# ECMeter-M0.net
KiCad netlist of a schematic drawn in EAGLE
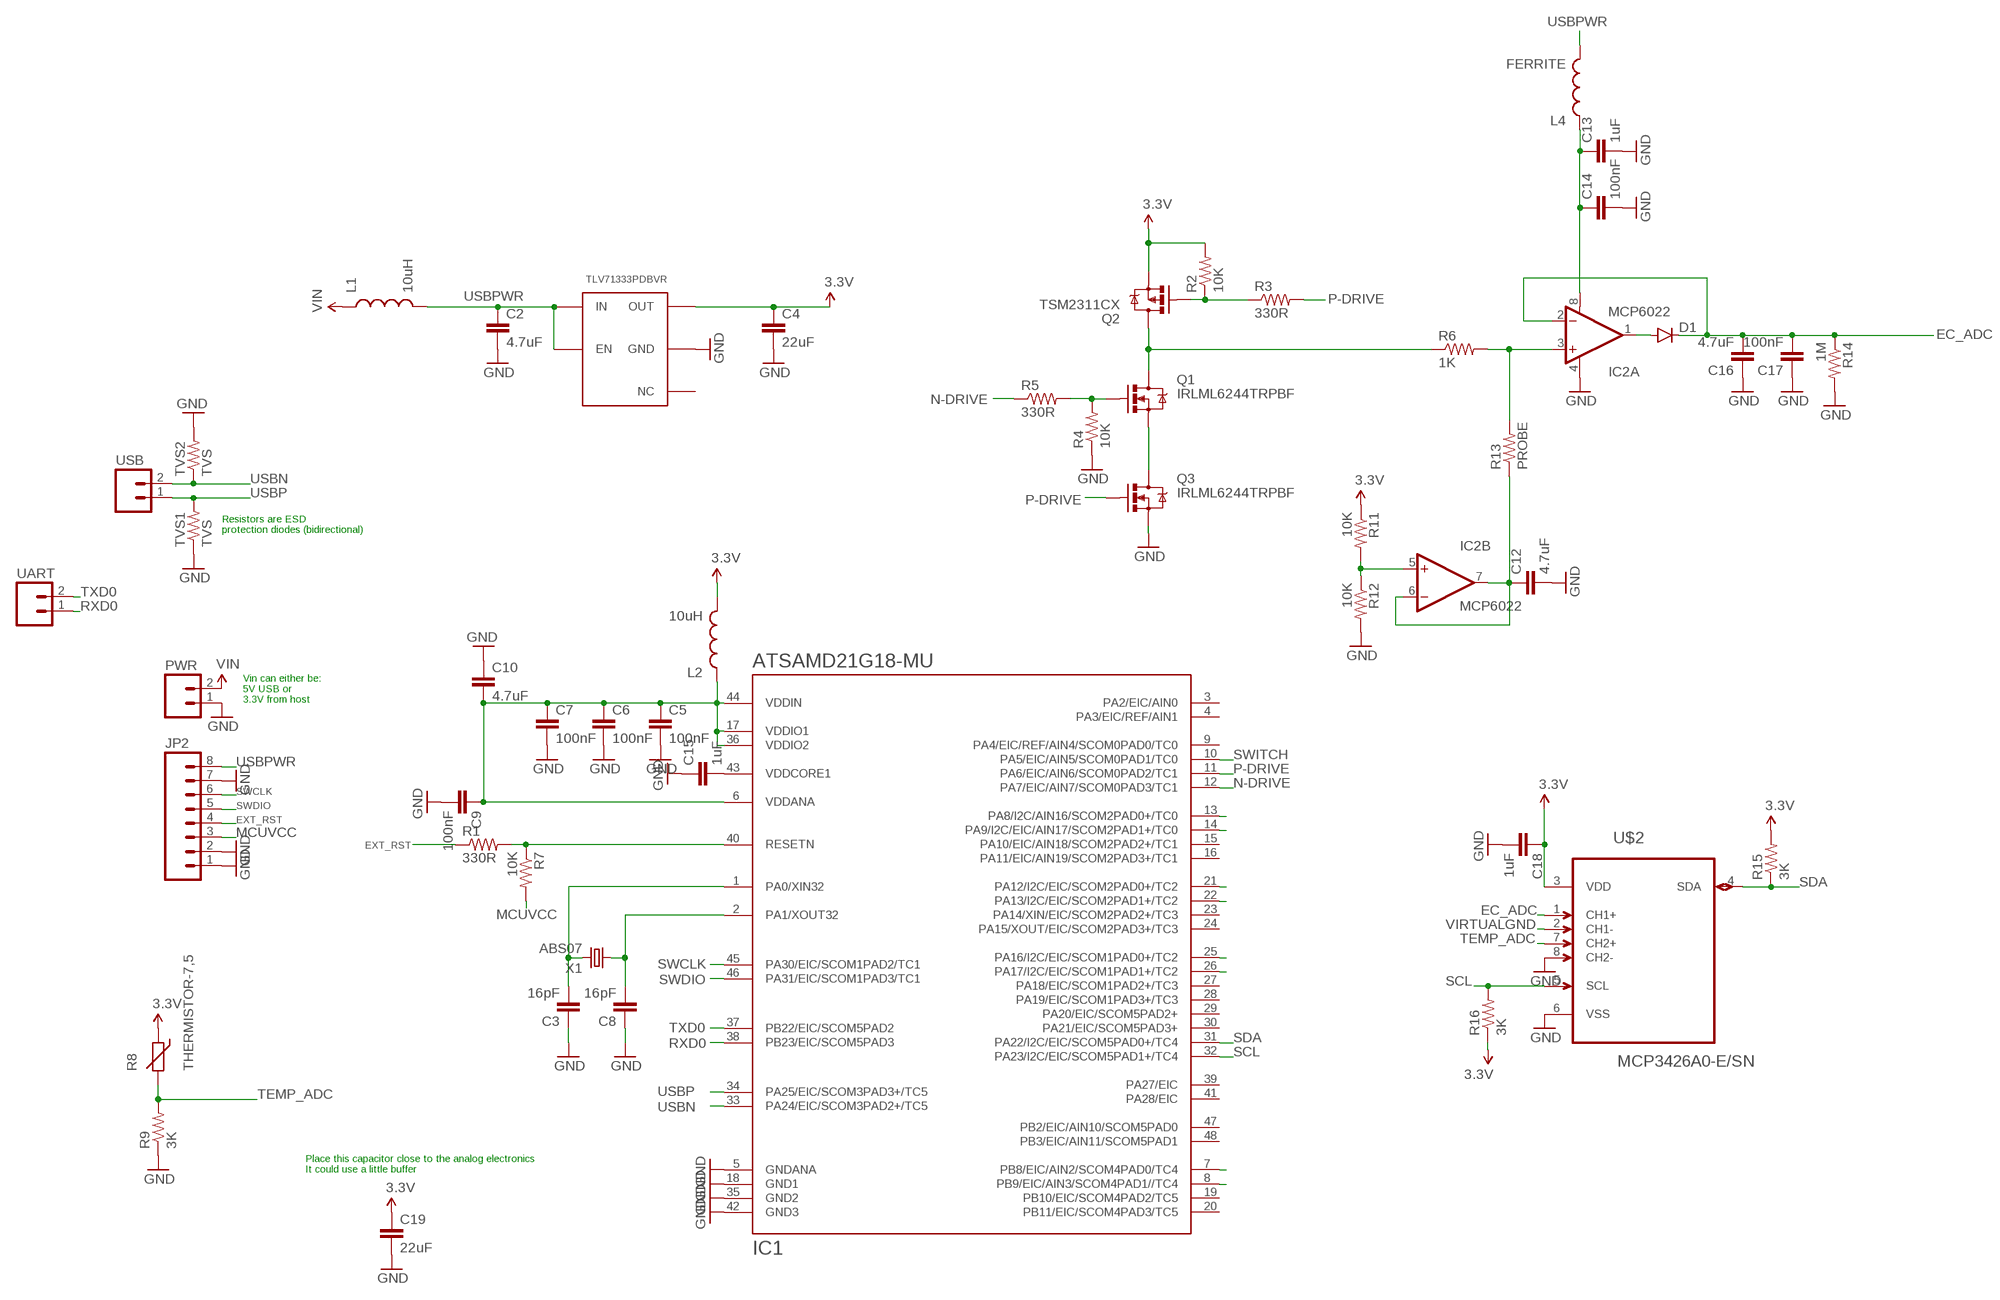
[diagram p0: schematic, sheet 1]

(export (version "E")
  (design (tool "Eeschema 10.0.6"))
  (components
    (comp (ref "C2")
      (value "4.7uF")
      (footprint "eagle-import:0805")
      (libsource (lib "eagle-import") (part "SparkFun-Passives_CAP0805"))
    )
    (comp (ref "C3")
      (value "16pF")
      (footprint "eagle-import:0402-CAP")
      (libsource (lib "eagle-import") (part "CAP0402-CAP"))
    )
    (comp (ref "C4")
      (value "22uF")
      (footprint "eagle-import:0805")
      (libsource (lib "eagle-import") (part "CAP0805"))
    )
    (comp (ref "C5")
      (value "100nF")
      (footprint "eagle-import:0603-CAP")
      (libsource (lib "eagle-import") (part "SparkFun-Passives_CAP0603-CAP"))
    )
    (comp (ref "C6")
      (value "100nF")
      (footprint "eagle-import:0603-CAP")
      (libsource (lib "eagle-import") (part "SparkFun-Passives_CAP0603-CAP"))
    )
    (comp (ref "C7")
      (value "100nF")
      (footprint "eagle-import:0603-CAP")
      (libsource (lib "eagle-import") (part "SparkFun-Passives_CAP0603-CAP"))
    )
    (comp (ref "C8")
      (value "16pF")
      (footprint "eagle-import:0402-CAP")
      (libsource (lib "eagle-import") (part "CAP0402-CAP"))
    )
    (comp (ref "C9")
      (value "100nF")
      (footprint "eagle-import:0603-CAP")
      (libsource (lib "eagle-import") (part "SparkFun-Passives_CAP0603-CAP"))
    )
    (comp (ref "C10")
      (value "4.7uF")
      (footprint "eagle-import:0805")
      (libsource (lib "eagle-import") (part "CAP0805"))
    )
    (comp (ref "C12")
      (value "4.7uF")
      (footprint "eagle-import:0805")
      (libsource (lib "eagle-import") (part "CAP0805"))
    )
    (comp (ref "C13")
      (value "1uF")
      (footprint "eagle-import:0603-CAP")
      (libsource (lib "eagle-import") (part "SparkFun-Passives_CAP0603-CAP"))
    )
    (comp (ref "C14")
      (value "100nF")
      (footprint "eagle-import:0603-CAP")
      (libsource (lib "eagle-import") (part "SparkFun-Passives_CAP0603-CAP"))
    )
    (comp (ref "C15")
      (value "1uF")
      (footprint "eagle-import:0603-CAP")
      (libsource (lib "eagle-import") (part "SparkFun-Passives_CAP0603-CAP"))
    )
    (comp (ref "C16")
      (value "4.7uF")
      (footprint "eagle-import:0805")
      (libsource (lib "eagle-import") (part "SparkFun-Passives_CAP0805"))
    )
    (comp (ref "C17")
      (value "100nF")
      (footprint "eagle-import:0603-CAP")
      (libsource (lib "eagle-import") (part "SparkFun-Passives_CAP0603-CAP"))
    )
    (comp (ref "C18")
      (value "1uF")
      (footprint "eagle-import:0603-CAP")
      (libsource (lib "eagle-import") (part "SparkFun-Passives_CAP0603-CAP"))
    )
    (comp (ref "C19")
      (value "22uF")
      (footprint "eagle-import:0805")
      (libsource (lib "eagle-import") (part "CAP0805"))
    )
    (comp (ref "D1")
      (value "DIODESOD123")
      (footprint "eagle-import:SOD-123")
      (libsource (lib "eagle-import") (part "DIODESOD123"))
    )
    (comp (ref "IC1")
      (value "ATSAMD21G18-MU")
      (footprint "eagle-import:QFN48")
      (libsource (lib "eagle-import") (part "ATSAMD21G18-MU"))
    )
    (comp (ref "IC2")
      (value "MCP6022")
      (footprint "eagle-import:SO08")
      (libsource (lib "eagle-import") (part "OPAMP-DUALU"))
    )
    (comp (ref "JP2")
      (value "M08NO_SILK_FEMALE_PTH")
      (footprint "eagle-import:1X08_NO_SILK")
      (libsource (lib "eagle-import") (part "M08NO_SILK_FEMALE_PTH"))
    )
    (comp (ref "L1")
      (value "10uH")
      (footprint "eagle-import:0805")
      (libsource (lib "eagle-import") (part "INDUCTOR0805"))
    )
    (comp (ref "L2")
      (value "10uH")
      (footprint "eagle-import:0805")
      (libsource (lib "eagle-import") (part "INDUCTOR0805"))
    )
    (comp (ref "L4")
      (value "FERRITE")
      (footprint "eagle-import:0603")
      (libsource (lib "eagle-import") (part "INDUCTOR0603"))
    )
    (comp (ref "PWR")
      (value "M02LOCK_LONGPADS")
      (footprint "eagle-import:1X02_LOCK_LONGPADS")
      (libsource (lib "eagle-import") (part "M02LOCK_LONGPADS"))
    )
    (comp (ref "Q1")
      (value "IRLML6244TRPBF")
      (footprint "eagle-import:SOT23-3")
      (libsource (lib "eagle-import") (part "MOSFET-NCHANNELAO3404A"))
    )
    (comp (ref "Q2")
      (value "TSM2311CX")
      (footprint "eagle-import:SOT23-3")
      (libsource (lib "eagle-import") (part "MOSFET-PCHANNEL"))
    )
    (comp (ref "Q3")
      (value "IRLML6244TRPBF")
      (footprint "eagle-import:SOT23-3")
      (libsource (lib "eagle-import") (part "MOSFET-NCHANNELAO3404A"))
    )
    (comp (ref "R1")
      (value "330R")
      (footprint "eagle-import:0603-RES")
      (libsource (lib "eagle-import") (part "SparkFun-Resistors_RESISTOR0603-RES"))
    )
    (comp (ref "R2")
      (value "10K")
      (footprint "eagle-import:0603-RES")
      (libsource (lib "eagle-import") (part "SparkFun-Resistors_RESISTOR0603-RES"))
    )
    (comp (ref "R3")
      (value "330R")
      (footprint "eagle-import:0603-RES")
      (libsource (lib "eagle-import") (part "SparkFun-Resistors_RESISTOR0603-RES"))
    )
    (comp (ref "R4")
      (value "10K")
      (footprint "eagle-import:0603-RES")
      (libsource (lib "eagle-import") (part "SparkFun-Resistors_RESISTOR0603-RES"))
    )
    (comp (ref "R5")
      (value "330R")
      (footprint "eagle-import:0603-RES")
      (libsource (lib "eagle-import") (part "SparkFun-Resistors_RESISTOR0603-RES"))
    )
    (comp (ref "R6")
      (value "1K")
      (footprint "eagle-import:1206")
      (libsource (lib "eagle-import") (part "SparkFun-Resistors_RESISTOR1206"))
    )
    (comp (ref "R7")
      (value "10K")
      (footprint "eagle-import:0603-RES")
      (libsource (lib "eagle-import") (part "SparkFun-Resistors_RESISTOR0603-RES"))
    )
    (comp (ref "R8")
      (value "THERMISTOR-7,5")
      (footprint "eagle-import:R-7,5")
      (libsource (lib "eagle-import") (part "THERMISTOR-7,5"))
    )
    (comp (ref "R9")
      (value "3K")
      (footprint "eagle-import:0603-RES")
      (libsource (lib "eagle-import") (part "SparkFun-Resistors_RESISTOR0603-RES"))
    )
    (comp (ref "R11")
      (value "10K")
      (footprint "eagle-import:0603-RES")
      (libsource (lib "eagle-import") (part "SparkFun-Resistors_RESISTOR0603-RES"))
    )
    (comp (ref "R12")
      (value "10K")
      (footprint "eagle-import:0603-RES")
      (libsource (lib "eagle-import") (part "SparkFun-Resistors_RESISTOR0603-RES"))
    )
    (comp (ref "R13")
      (value "PROBE")
      (footprint "eagle-import:AXIAL-0.6")
      (libsource (lib "eagle-import") (part "RESISTORPTH-1W"))
    )
    (comp (ref "R14")
      (value "1M")
      (footprint "eagle-import:0603-RES")
      (libsource (lib "eagle-import") (part "SparkFun-Resistors_RESISTOR0603-RES"))
    )
    (comp (ref "R15")
      (value "3K")
      (footprint "eagle-import:0603-RES")
      (libsource (lib "eagle-import") (part "SparkFun-Resistors_RESISTOR0603-RES"))
    )
    (comp (ref "R16")
      (value "3K")
      (footprint "eagle-import:0603-RES")
      (libsource (lib "eagle-import") (part "SparkFun-Resistors_RESISTOR0603-RES"))
    )
    (comp (ref "TVS1")
      (value "TVS")
      (footprint "eagle-import:0603-RES")
      (libsource (lib "eagle-import") (part "RESISTOR0603-RES"))
    )
    (comp (ref "TVS2")
      (value "TVS")
      (footprint "eagle-import:0603-RES")
      (libsource (lib "eagle-import") (part "RESISTOR0603-RES"))
    )
    (comp (ref "U$1")
      (value "TLV71333PDBVR")
      (footprint "eagle-import:TLV71333PDBVR")
      (libsource (lib "eagle-import") (part "TLV71333PDBVR"))
    )
    (comp (ref "U$2")
      (value "MCP3426A0-E/SN")
      (footprint "eagle-import:SOIC127P600X175-8N")
      (libsource (lib "eagle-import") (part "MCP3426A0-E/SN"))
    )
    (comp (ref "UART")
      (value "M02LOCK_LONGPADS")
      (footprint "eagle-import:1X02_LOCK_LONGPADS")
      (libsource (lib "eagle-import") (part "M02LOCK_LONGPADS"))
    )
    (comp (ref "USB")
      (value "M02LOCK_LONGPADS")
      (footprint "eagle-import:1X02_LOCK_LONGPADS")
      (libsource (lib "eagle-import") (part "M02LOCK_LONGPADS"))
    )
    (comp (ref "X1")
      (value "ABS07")
      (footprint "eagle-import:ABS07")
      (libsource (lib "eagle-import") (part "ABS07"))
    )
  )
  (nets
    (net (code "1") (name "/EC_ADC") (class "Default")
      (node (ref "C16") (pin "2") (pinfunction "2_2") (pintype "passive"))
      (node (ref "C17") (pin "2") (pinfunction "2_2") (pintype "passive"))
      (node (ref "D1") (pin "C") (pinfunction "C_C") (pintype "passive"))
      (node (ref "IC2") (pin "2") (pinfunction "-IN_2") (pintype "input"))
      (node (ref "R14") (pin "1") (pinfunction "1_1") (pintype "passive"))
      (node (ref "U$2") (pin "1") (pinfunction "CH1+_1") (pintype "input"))
    )
    (net (code "2") (name "/EXT_RST") (class "Default")
      (node (ref "JP2") (pin "4") (pinfunction "4_4") (pintype "passive"))
      (node (ref "R1") (pin "1") (pinfunction "1_1") (pintype "passive"))
    )
    (net (code "3") (name "/MCUVCC") (class "Default")
      (node (ref "C10") (pin "2") (pinfunction "2_2") (pintype "passive"))
      (node (ref "C5") (pin "1") (pinfunction "1_1") (pintype "passive"))
      (node (ref "C6") (pin "1") (pinfunction "1_1") (pintype "passive"))
      (node (ref "C7") (pin "1") (pinfunction "1_1") (pintype "passive"))
      (node (ref "C9") (pin "1") (pinfunction "1_1") (pintype "passive"))
      (node (ref "IC1") (pin "17") (pinfunction "VDDIO1_17") (pintype "power_in"))
      (node (ref "IC1") (pin "36") (pinfunction "VDDIO2_36") (pintype "power_in"))
      (node (ref "IC1") (pin "44") (pinfunction "VDDIN_44") (pintype "power_in"))
      (node (ref "IC1") (pin "6") (pinfunction "VDDANA_6") (pintype "power_in"))
      (node (ref "JP2") (pin "3") (pinfunction "3_3") (pintype "passive"))
      (node (ref "L2") (pin "1") (pinfunction "1_1") (pintype "passive"))
      (node (ref "R7") (pin "2") (pinfunction "2_2") (pintype "passive"))
    )
    (net (code "4") (name "/N-DRIVE") (class "Default")
      (node (ref "IC1") (pin "12") (pinfunction "PA7/EIC/AIN7/SCOM0PAD3/TC1_12") (pintype "bidirectional"))
      (node (ref "R5") (pin "1") (pinfunction "1_1") (pintype "passive"))
    )
    (net (code "5") (name "/P-DRIVE") (class "Default")
      (node (ref "IC1") (pin "11") (pinfunction "PA6/EIC/AIN6/SCOM0PAD2/TC1_11") (pintype "bidirectional"))
      (node (ref "Q3") (pin "1") (pinfunction "G_1") (pintype "passive"))
      (node (ref "R3") (pin "2") (pinfunction "2_2") (pintype "passive"))
    )
    (net (code "6") (name "/RXD0") (class "Default")
      (node (ref "IC1") (pin "38") (pinfunction "PB23/EIC/SCOM5PAD3_38") (pintype "bidirectional"))
      (node (ref "UART") (pin "1") (pinfunction "1_1") (pintype "passive"))
    )
    (net (code "7") (name "/SCL") (class "Default")
      (node (ref "IC1") (pin "32") (pinfunction "PA23/I2C/EIC/SCOM5PAD1+/TC4_32") (pintype "bidirectional"))
      (node (ref "R16") (pin "2") (pinfunction "2_2") (pintype "passive"))
      (node (ref "U$2") (pin "5") (pinfunction "SCL_5") (pintype "input"))
    )
    (net (code "8") (name "/SDA") (class "Default")
      (node (ref "IC1") (pin "31") (pinfunction "PA22/I2C/EIC/SCOM5PAD0+/TC4_31") (pintype "bidirectional"))
      (node (ref "R15") (pin "1") (pinfunction "1_1") (pintype "passive"))
      (node (ref "U$2") (pin "4") (pinfunction "SDA_4") (pintype "bidirectional"))
    )
    (net (code "9") (name "/SWCLK") (class "Default")
      (node (ref "IC1") (pin "45") (pinfunction "PA30/EIC/SCOM1PAD2/TC1_45") (pintype "bidirectional"))
      (node (ref "JP2") (pin "6") (pinfunction "6_6") (pintype "passive"))
    )
    (net (code "10") (name "/SWDIO") (class "Default")
      (node (ref "IC1") (pin "46") (pinfunction "PA31/EIC/SCOM1PAD3/TC1_46") (pintype "bidirectional"))
      (node (ref "JP2") (pin "5") (pinfunction "5_5") (pintype "passive"))
    )
    (net (code "11") (name "/SWITCH") (class "Default")
      (node (ref "IC1") (pin "10") (pinfunction "PA5/EIC/AIN5/SCOM0PAD1/TC0_10") (pintype "bidirectional"))
    )
    (net (code "12") (name "/TEMP_ADC") (class "Default")
      (node (ref "R8") (pin "2") (pinfunction "2_2") (pintype "passive"))
      (node (ref "R9") (pin "2") (pinfunction "2_2") (pintype "passive"))
      (node (ref "U$2") (pin "7") (pinfunction "CH2+_7") (pintype "input"))
    )
    (net (code "13") (name "/TXD0") (class "Default")
      (node (ref "IC1") (pin "37") (pinfunction "PB22/EIC/SCOM5PAD2_37") (pintype "bidirectional"))
      (node (ref "UART") (pin "2") (pinfunction "2_2") (pintype "passive"))
    )
    (net (code "14") (name "/USBN") (class "Default")
      (node (ref "IC1") (pin "33") (pinfunction "PA24/EIC/SCOM3PAD2+/TC5_33") (pintype "bidirectional"))
      (node (ref "TVS2") (pin "1") (pinfunction "1_1") (pintype "passive"))
      (node (ref "USB") (pin "2") (pinfunction "2_2") (pintype "passive"))
    )
    (net (code "15") (name "/USBP") (class "Default")
      (node (ref "IC1") (pin "34") (pinfunction "PA25/EIC/SCOM3PAD3+/TC5_34") (pintype "bidirectional"))
      (node (ref "TVS1") (pin "2") (pinfunction "2_2") (pintype "passive"))
      (node (ref "USB") (pin "1") (pinfunction "1_1") (pintype "passive"))
    )
    (net (code "16") (name "/USBPWR") (class "Default")
      (node (ref "C2") (pin "1") (pinfunction "1_1") (pintype "passive"))
      (node (ref "JP2") (pin "8") (pinfunction "8_8") (pintype "passive"))
      (node (ref "L1") (pin "2") (pinfunction "2_2") (pintype "passive"))
      (node (ref "L4") (pin "2") (pinfunction "2_2") (pintype "passive"))
      (node (ref "U$1") (pin "P$1") (pinfunction "IN_P$1") (pintype "bidirectional"))
      (node (ref "U$1") (pin "P$3") (pinfunction "EN_P$3") (pintype "bidirectional"))
    )
    (net (code "17") (name "/VIRTUALGND") (class "Default")
      (node (ref "C12") (pin "1") (pinfunction "1_1") (pintype "passive"))
      (node (ref "IC2") (pin "6") (pinfunction "-IN_6") (pintype "input"))
      (node (ref "IC2") (pin "7") (pinfunction "OUT_7") (pintype "output"))
      (node (ref "R13") (pin "P$1") (pinfunction "1_P$1") (pintype "passive"))
      (node (ref "U$2") (pin "2") (pinfunction "CH1-_2") (pintype "input"))
    )
    (net (code "18") (name "3.3V") (class "Default")
      (node (ref "C18") (pin "1") (pinfunction "1_1") (pintype "passive"))
      (node (ref "C19") (pin "1") (pinfunction "1_1") (pintype "passive"))
      (node (ref "C4") (pin "1") (pinfunction "1_1") (pintype "passive"))
      (node (ref "L2") (pin "2") (pinfunction "2_2") (pintype "passive"))
      (node (ref "Q2") (pin "2") (pinfunction "S_2") (pintype "passive"))
      (node (ref "R11") (pin "1") (pinfunction "1_1") (pintype "passive"))
      (node (ref "R15") (pin "2") (pinfunction "2_2") (pintype "passive"))
      (node (ref "R16") (pin "1") (pinfunction "1_1") (pintype "passive"))
      (node (ref "R2") (pin "2") (pinfunction "2_2") (pintype "passive"))
      (node (ref "R8") (pin "1") (pinfunction "1_1") (pintype "passive"))
      (node (ref "U$1") (pin "P$5") (pinfunction "OUT_P$5") (pintype "bidirectional"))
      (node (ref "U$2") (pin "3") (pinfunction "VDD_3") (pintype "power_in"))
    )
    (net (code "19") (name "GND") (class "Default")
      (node (ref "C10") (pin "1") (pinfunction "1_1") (pintype "passive"))
      (node (ref "C12") (pin "2") (pinfunction "2_2") (pintype "passive"))
      (node (ref "C13") (pin "2") (pinfunction "2_2") (pintype "passive"))
      (node (ref "C14") (pin "2") (pinfunction "2_2") (pintype "passive"))
      (node (ref "C15") (pin "1") (pinfunction "1_1") (pintype "passive"))
      (node (ref "C16") (pin "1") (pinfunction "1_1") (pintype "passive"))
      (node (ref "C17") (pin "1") (pinfunction "1_1") (pintype "passive"))
      (node (ref "C18") (pin "2") (pinfunction "2_2") (pintype "passive"))
      (node (ref "C19") (pin "2") (pinfunction "2_2") (pintype "passive"))
      (node (ref "C2") (pin "2") (pinfunction "2_2") (pintype "passive"))
      (node (ref "C3") (pin "1") (pinfunction "1_1") (pintype "passive"))
      (node (ref "C4") (pin "2") (pinfunction "2_2") (pintype "passive"))
      (node (ref "C5") (pin "2") (pinfunction "2_2") (pintype "passive"))
      (node (ref "C6") (pin "2") (pinfunction "2_2") (pintype "passive"))
      (node (ref "C7") (pin "2") (pinfunction "2_2") (pintype "passive"))
      (node (ref "C8") (pin "1") (pinfunction "1_1") (pintype "passive"))
      (node (ref "C9") (pin "2") (pinfunction "2_2") (pintype "passive"))
      (node (ref "IC1") (pin "18") (pinfunction "GND1_18") (pintype "power_in"))
      (node (ref "IC1") (pin "35") (pinfunction "GND2_35") (pintype "power_in"))
      (node (ref "IC1") (pin "42") (pinfunction "GND3_42") (pintype "power_in"))
      (node (ref "IC1") (pin "5") (pinfunction "GNDANA_5") (pintype "power_in"))
      (node (ref "IC2") (pin "4") (pinfunction "V-_4") (pintype "power_in"))
      (node (ref "JP2") (pin "1") (pinfunction "1_1") (pintype "passive"))
      (node (ref "JP2") (pin "2") (pinfunction "2_2") (pintype "passive"))
      (node (ref "JP2") (pin "7") (pinfunction "7_7") (pintype "passive"))
      (node (ref "PWR") (pin "1") (pinfunction "1_1") (pintype "passive"))
      (node (ref "Q3") (pin "2") (pinfunction "S_2") (pintype "passive"))
      (node (ref "R12") (pin "2") (pinfunction "2_2") (pintype "passive"))
      (node (ref "R14") (pin "2") (pinfunction "2_2") (pintype "passive"))
      (node (ref "R4") (pin "1") (pinfunction "1_1") (pintype "passive"))
      (node (ref "R9") (pin "1") (pinfunction "1_1") (pintype "passive"))
      (node (ref "TVS1") (pin "1") (pinfunction "1_1") (pintype "passive"))
      (node (ref "TVS2") (pin "2") (pinfunction "2_2") (pintype "passive"))
      (node (ref "U$1") (pin "P$2") (pinfunction "GND_P$2") (pintype "bidirectional"))
      (node (ref "U$2") (pin "6") (pinfunction "VSS_6") (pintype "power_in"))
      (node (ref "U$2") (pin "8") (pinfunction "CH2-_8") (pintype "input"))
    )
    (net (code "20") (name "Net-(IC1-PA0{slash}XIN32)") (class "Default")
      (node (ref "C3") (pin "2") (pinfunction "2_2") (pintype "passive"))
      (node (ref "IC1") (pin "1") (pinfunction "PA0/XIN32_1") (pintype "bidirectional"))
      (node (ref "X1") (pin "P$2") (pinfunction "2_P$2") (pintype "passive"))
    )
    (net (code "21") (name "Net-(IC1-PA1{slash}XOUT32)") (class "Default")
      (node (ref "C8") (pin "2") (pinfunction "2_2") (pintype "passive"))
      (node (ref "IC1") (pin "2") (pinfunction "PA1/XOUT32_2") (pintype "bidirectional"))
      (node (ref "X1") (pin "P$1") (pinfunction "1_P$1") (pintype "passive"))
    )
    (net (code "22") (name "Net-(IC1-RESETN)") (class "Default")
      (node (ref "IC1") (pin "40") (pinfunction "RESETN_40") (pintype "bidirectional"))
      (node (ref "R1") (pin "2") (pinfunction "2_2") (pintype "passive"))
      (node (ref "R7") (pin "1") (pinfunction "1_1") (pintype "passive"))
    )
    (net (code "23") (name "Net-(IC1-VDDCORE1)") (class "Default")
      (node (ref "C15") (pin "2") (pinfunction "2_2") (pintype "passive"))
      (node (ref "IC1") (pin "43") (pinfunction "VDDCORE1_43") (pintype "input"))
    )
    (net (code "24") (name "Net-(IC2A-+IN)") (class "Default")
      (node (ref "IC2") (pin "3") (pinfunction "+IN_3") (pintype "input"))
      (node (ref "R13") (pin "P$2") (pinfunction "2_P$2") (pintype "passive"))
      (node (ref "R6") (pin "2") (pinfunction "2_2") (pintype "passive"))
    )
    (net (code "25") (name "Net-(IC2A-OUT)") (class "Default")
      (node (ref "D1") (pin "A") (pinfunction "A_A") (pintype "passive"))
      (node (ref "IC2") (pin "1") (pinfunction "OUT_1") (pintype "output"))
    )
    (net (code "26") (name "Net-(IC2A-V+)") (class "Default")
      (node (ref "C13") (pin "1") (pinfunction "1_1") (pintype "passive"))
      (node (ref "C14") (pin "1") (pinfunction "1_1") (pintype "passive"))
      (node (ref "IC2") (pin "8") (pinfunction "V+_8") (pintype "power_in"))
      (node (ref "L4") (pin "1") (pinfunction "1_1") (pintype "passive"))
    )
    (net (code "27") (name "Net-(IC2B-+IN)") (class "Default")
      (node (ref "IC2") (pin "5") (pinfunction "+IN_5") (pintype "input"))
      (node (ref "R11") (pin "2") (pinfunction "2_2") (pintype "passive"))
      (node (ref "R12") (pin "1") (pinfunction "1_1") (pintype "passive"))
    )
    (net (code "28") (name "Net-(Q1-D)") (class "Default")
      (node (ref "Q1") (pin "3") (pinfunction "D_3") (pintype "passive"))
      (node (ref "Q2") (pin "3") (pinfunction "D_3") (pintype "passive"))
      (node (ref "R6") (pin "1") (pinfunction "1_1") (pintype "passive"))
    )
    (net (code "29") (name "Net-(Q1-G)") (class "Default")
      (node (ref "Q1") (pin "1") (pinfunction "G_1") (pintype "passive"))
      (node (ref "R4") (pin "2") (pinfunction "2_2") (pintype "passive"))
      (node (ref "R5") (pin "2") (pinfunction "2_2") (pintype "passive"))
    )
    (net (code "30") (name "Net-(Q1-S)") (class "Default")
      (node (ref "Q1") (pin "2") (pinfunction "S_2") (pintype "passive"))
      (node (ref "Q3") (pin "3") (pinfunction "D_3") (pintype "passive"))
    )
    (net (code "31") (name "Net-(Q2-G)") (class "Default")
      (node (ref "Q2") (pin "1") (pinfunction "G_1") (pintype "passive"))
      (node (ref "R2") (pin "1") (pinfunction "1_1") (pintype "passive"))
      (node (ref "R3") (pin "1") (pinfunction "1_1") (pintype "passive"))
    )
    (net (code "32") (name "VIN") (class "Default")
      (node (ref "L1") (pin "1") (pinfunction "1_1") (pintype "passive"))
      (node (ref "PWR") (pin "2") (pinfunction "2_2") (pintype "passive"))
    )
    (net (code "33") (name "unconnected-(IC1-PA2{slash}EIC{slash}AIN0-Pad3)") (class "Default")
      (node (ref "IC1") (pin "3") (pinfunction "PA2/EIC/AIN0_3") (pintype "bidirectional"))
    )
    (net (code "34") (name "unconnected-(IC1-PA3{slash}EIC{slash}REF{slash}AIN1-Pad4)") (class "Default")
      (node (ref "IC1") (pin "4") (pinfunction "PA3/EIC/REF/AIN1_4") (pintype "bidirectional"))
    )
    (net (code "35") (name "unconnected-(IC1-PA4{slash}EIC{slash}REF{slash}AIN4{slash}SCOM0PAD0{slash}TC0-Pad9)") (class "Default")
      (node (ref "IC1") (pin "9") (pinfunction "PA4/EIC/REF/AIN4/SCOM0PAD0/TC0_9") (pintype "bidirectional"))
    )
    (net (code "36") (name "unconnected-(IC1-PA8{slash}I2C{slash}AIN16{slash}SCOM2PAD0+{slash}TC0-Pad13)") (class "Default")
      (node (ref "IC1") (pin "13") (pinfunction "PA8/I2C/AIN16/SCOM2PAD0+/TC0_13") (pintype "bidirectional"))
    )
    (net (code "37") (name "unconnected-(IC1-PA9{slash}I2C{slash}EIC{slash}AIN17{slash}SCOM2PAD1+{slash}TC0-Pad14)") (class "Default")
      (node (ref "IC1") (pin "14") (pinfunction "PA9/I2C/EIC/AIN17/SCOM2PAD1+/TC0_14") (pintype "bidirectional"))
    )
    (net (code "38") (name "unconnected-(IC1-PA10{slash}EIC{slash}AIN18{slash}SCOM2PAD2+{slash}TC1-Pad15)") (class "Default")
      (node (ref "IC1") (pin "15") (pinfunction "PA10/EIC/AIN18/SCOM2PAD2+/TC1_15") (pintype "bidirectional"))
    )
    (net (code "39") (name "unconnected-(IC1-PA11{slash}EIC{slash}AIN19{slash}SCOM2PAD3+{slash}TC1-Pad16)") (class "Default")
      (node (ref "IC1") (pin "16") (pinfunction "PA11/EIC/AIN19/SCOM2PAD3+/TC1_16") (pintype "bidirectional"))
    )
    (net (code "40") (name "unconnected-(IC1-PA12{slash}I2C{slash}EIC{slash}SCOM2PAD0+{slash}TC2-Pad21)") (class "Default")
      (node (ref "IC1") (pin "21") (pinfunction "PA12/I2C/EIC/SCOM2PAD0+/TC2_21") (pintype "bidirectional"))
    )
    (net (code "41") (name "unconnected-(IC1-PA13{slash}I2C{slash}EIC{slash}SCOM2PAD1+{slash}TC2-Pad22)") (class "Default")
      (node (ref "IC1") (pin "22") (pinfunction "PA13/I2C/EIC/SCOM2PAD1+/TC2_22") (pintype "bidirectional"))
    )
    (net (code "42") (name "unconnected-(IC1-PA14{slash}XIN{slash}EIC{slash}SCOM2PAD2+{slash}TC3-Pad23)") (class "Default")
      (node (ref "IC1") (pin "23") (pinfunction "PA14/XIN/EIC/SCOM2PAD2+/TC3_23") (pintype "bidirectional"))
    )
    (net (code "43") (name "unconnected-(IC1-PA15{slash}XOUT{slash}EIC{slash}SCOM2PAD3+{slash}TC3-Pad24)") (class "Default")
      (node (ref "IC1") (pin "24") (pinfunction "PA15/XOUT/EIC/SCOM2PAD3+/TC3_24") (pintype "bidirectional"))
    )
    (net (code "44") (name "unconnected-(IC1-PA16{slash}I2C{slash}EIC{slash}SCOM1PAD0+{slash}TC2-Pad25)") (class "Default")
      (node (ref "IC1") (pin "25") (pinfunction "PA16/I2C/EIC/SCOM1PAD0+/TC2_25") (pintype "bidirectional"))
    )
    (net (code "45") (name "unconnected-(IC1-PA17{slash}I2C{slash}EIC{slash}SCOM1PAD1+{slash}TC2-Pad26)") (class "Default")
      (node (ref "IC1") (pin "26") (pinfunction "PA17/I2C/EIC/SCOM1PAD1+/TC2_26") (pintype "bidirectional"))
    )
    (net (code "46") (name "unconnected-(IC1-PA18{slash}EIC{slash}SCOM1PAD2+{slash}TC3-Pad27)") (class "Default")
      (node (ref "IC1") (pin "27") (pinfunction "PA18/EIC/SCOM1PAD2+/TC3_27") (pintype "bidirectional"))
    )
    (net (code "47") (name "unconnected-(IC1-PA19{slash}EIC{slash}SCOM1PAD3+{slash}TC3-Pad28)") (class "Default")
      (node (ref "IC1") (pin "28") (pinfunction "PA19/EIC/SCOM1PAD3+/TC3_28") (pintype "bidirectional"))
    )
    (net (code "48") (name "unconnected-(IC1-PA20{slash}EIC{slash}SCOM5PAD2+-Pad29)") (class "Default")
      (node (ref "IC1") (pin "29") (pinfunction "PA20/EIC/SCOM5PAD2+_29") (pintype "bidirectional"))
    )
    (net (code "49") (name "unconnected-(IC1-PA21{slash}EIC{slash}SCOM5PAD3+-Pad30)") (class "Default")
      (node (ref "IC1") (pin "30") (pinfunction "PA21/EIC/SCOM5PAD3+_30") (pintype "bidirectional"))
    )
    (net (code "50") (name "unconnected-(IC1-PA27{slash}EIC-Pad39)") (class "Default")
      (node (ref "IC1") (pin "39") (pinfunction "PA27/EIC_39") (pintype "bidirectional"))
    )
    (net (code "51") (name "unconnected-(IC1-PA28{slash}EIC-Pad41)") (class "Default")
      (node (ref "IC1") (pin "41") (pinfunction "PA28/EIC_41") (pintype "bidirectional"))
    )
    (net (code "52") (name "unconnected-(IC1-PB2{slash}EIC{slash}AIN10{slash}SCOM5PAD0-Pad47)") (class "Default")
      (node (ref "IC1") (pin "47") (pinfunction "PB2/EIC/AIN10/SCOM5PAD0_47") (pintype "bidirectional"))
    )
    (net (code "53") (name "unconnected-(IC1-PB3{slash}EIC{slash}AIN11{slash}SCOM5PAD1-Pad48)") (class "Default")
      (node (ref "IC1") (pin "48") (pinfunction "PB3/EIC/AIN11/SCOM5PAD1_48") (pintype "bidirectional"))
    )
    (net (code "54") (name "unconnected-(IC1-PB8{slash}EIC{slash}AIN2{slash}SCOM4PAD0{slash}TC4-Pad7)") (class "Default")
      (node (ref "IC1") (pin "7") (pinfunction "PB8/EIC/AIN2/SCOM4PAD0/TC4_7") (pintype "bidirectional"))
    )
    (net (code "55") (name "unconnected-(IC1-PB9{slash}EIC{slash}AIN3{slash}SCOM4PAD1{slash}{slash}TC4-Pad8)") (class "Default")
      (node (ref "IC1") (pin "8") (pinfunction "PB9/EIC/AIN3/SCOM4PAD1//TC4_8") (pintype "bidirectional"))
    )
    (net (code "56") (name "unconnected-(IC1-PB10{slash}EIC{slash}SCOM4PAD2{slash}TC5-Pad19)") (class "Default")
      (node (ref "IC1") (pin "19") (pinfunction "PB10/EIC/SCOM4PAD2/TC5_19") (pintype "bidirectional"))
    )
    (net (code "57") (name "unconnected-(IC1-PB11{slash}EIC{slash}SCOM4PAD3{slash}TC5-Pad20)") (class "Default")
      (node (ref "IC1") (pin "20") (pinfunction "PB11/EIC/SCOM4PAD3/TC5_20") (pintype "bidirectional"))
    )
    (net (code "58") (name "unconnected-(U$1-NC-PadP$4)") (class "Default")
      (node (ref "U$1") (pin "P$4") (pinfunction "NC_P$4") (pintype "bidirectional"))
    )
  )
)
